# BT_board.net
KiCad netlist of a schematic drawn in EAGLE
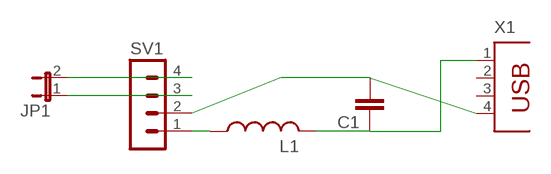
[diagram p0: schematic, sheet 1]

(export (version "E")
  (design (tool "Eeschema 10.0.6"))
  (components
    (comp (ref "C1")
      (value "C5/2.5")
      (footprint "eagle-import:C5B2.5")
      (libsource (lib "eagle-import") (part "C5/2.5"))
    )
    (comp (ref "JP1")
      (value "JP1E")
      (footprint "eagle-import:JP1")
      (libsource (lib "eagle-import") (part "JP1E"))
    )
    (comp (ref "L1")
      (value "L-US0204V")
      (footprint "eagle-import:0204V")
      (libsource (lib "eagle-import") (part "L-US0204V"))
    )
    (comp (ref "SV1")
      (value "MA04-1")
      (footprint "eagle-import:MA04-1")
      (libsource (lib "eagle-import") (part "MA04-1"))
    )
    (comp (ref "X1")
      (value "PN87520")
      (footprint "eagle-import:PN87520")
      (libsource (lib "eagle-import") (part "PN87520"))
    )
  )
  (nets
    (net (code "1") (name "Net-(C1-Pad1)") (class "Default")
      (node (ref "C1") (pin "1") (pinfunction "1_1") (pintype "passive"))
      (node (ref "L1") (pin "2") (pinfunction "2_2") (pintype "passive"))
      (node (ref "X1") (pin "1") (pinfunction "1_1") (pintype "passive"))
    )
    (net (code "2") (name "Net-(C1-Pad2)") (class "Default")
      (node (ref "C1") (pin "2") (pinfunction "2_2") (pintype "passive"))
      (node (ref "SV1") (pin "2") (pinfunction "2_2") (pintype "passive"))
      (node (ref "X1") (pin "4") (pinfunction "4_4") (pintype "passive"))
    )
    (net (code "3") (name "Net-(JP1-Pad1)") (class "Default")
      (node (ref "JP1") (pin "1") (pinfunction "1_1") (pintype "passive"))
      (node (ref "SV1") (pin "3") (pinfunction "3_3") (pintype "passive"))
    )
    (net (code "4") (name "Net-(JP1-Pad2)") (class "Default")
      (node (ref "JP1") (pin "2") (pinfunction "2_2") (pintype "passive"))
      (node (ref "SV1") (pin "4") (pinfunction "4_4") (pintype "passive"))
    )
    (net (code "5") (name "Net-(L1-Pad1)") (class "Default")
      (node (ref "L1") (pin "1") (pinfunction "1_1") (pintype "passive"))
      (node (ref "SV1") (pin "1") (pinfunction "1_1") (pintype "passive"))
    )
    (net (code "6") (name "unconnected-(X1-Pad2)") (class "Default")
      (node (ref "X1") (pin "2") (pinfunction "2_2") (pintype "passive"))
    )
    (net (code "7") (name "unconnected-(X1-Pad3)") (class "Default")
      (node (ref "X1") (pin "3") (pinfunction "3_3") (pintype "passive"))
    )
  )
)
